# Busboard_v4.net
KiCad netlist of a schematic drawn in EAGLE
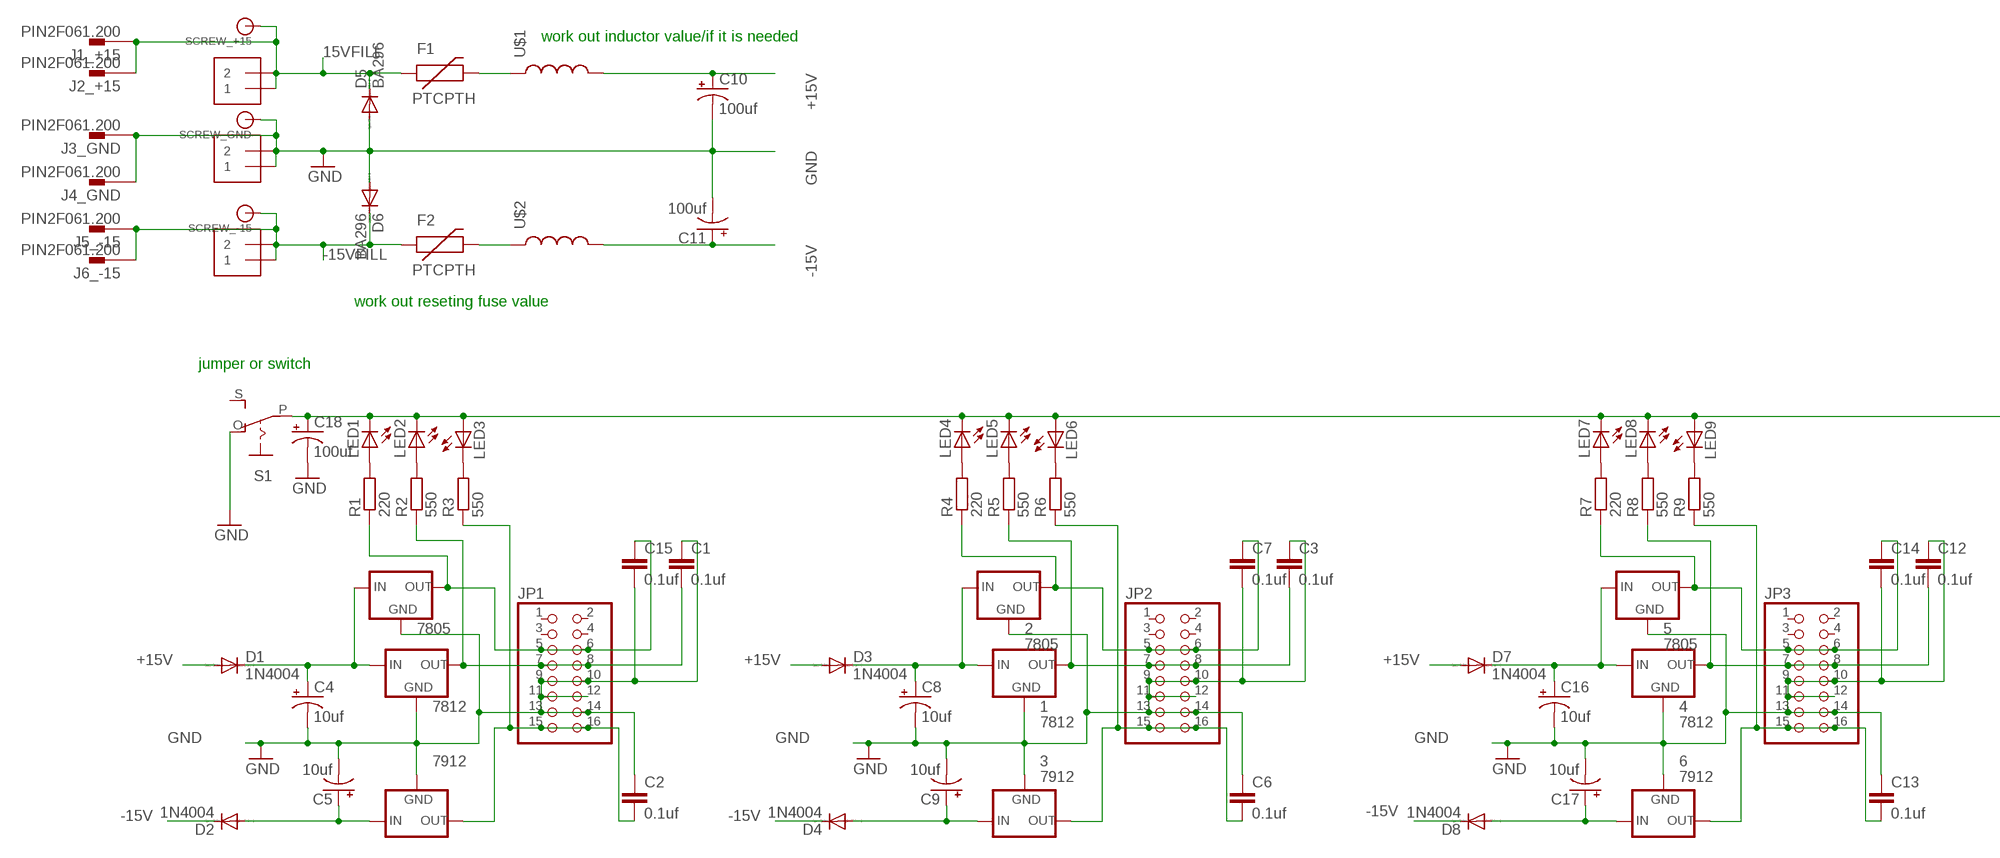
[diagram p0: schematic, sheet 1, part 1 of 2]
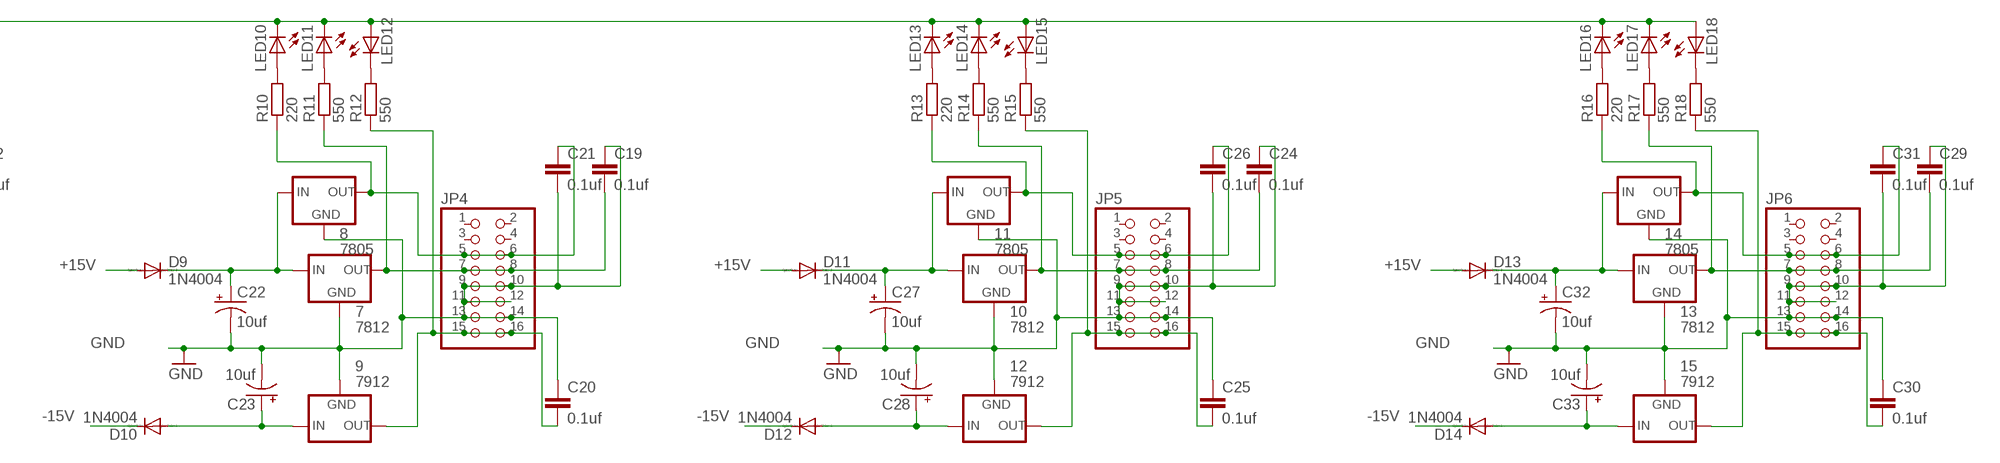
[diagram p1: schematic, sheet 1, part 2 of 2]

(export (version "E")
  (design (tool "Eeschema 10.0.6"))
  (components
    (comp (ref "+15V_DC_IN")
      (value "1X2-3.5MM")
      (footprint "eagle-import:1X2-3.5MM")
      (libsource (lib "eagle-import") (part "1X2-3.5MM"))
    )
    (comp (ref "-15V_DC_IN")
      (value "1X2-3.5MM")
      (footprint "eagle-import:1X2-3.5MM")
      (libsource (lib "eagle-import") (part "1X2-3.5MM"))
    )
    (comp (ref "1")
      (value "7812")
      (footprint "eagle-import:78MXXS")
      (libsource (lib "eagle-import") (part "78MXXS"))
    )
    (comp (ref "2")
      (value "7805")
      (footprint "eagle-import:78MXXS")
      (libsource (lib "eagle-import") (part "78MXXS"))
    )
    (comp (ref "3")
      (value "7912")
      (footprint "eagle-import:79XXS")
      (libsource (lib "eagle-import") (part "79XXS"))
    )
    (comp (ref "4")
      (value "7812")
      (footprint "eagle-import:78MXXS")
      (libsource (lib "eagle-import") (part "78MXXS"))
    )
    (comp (ref "5")
      (value "7805")
      (footprint "eagle-import:78MXXS")
      (libsource (lib "eagle-import") (part "78MXXS"))
    )
    (comp (ref "6")
      (value "7912")
      (footprint "eagle-import:79XXS")
      (libsource (lib "eagle-import") (part "79XXS"))
    )
    (comp (ref "7")
      (value "7812")
      (footprint "eagle-import:78MXXS")
      (libsource (lib "eagle-import") (part "78MXXS"))
    )
    (comp (ref "8")
      (value "7805")
      (footprint "eagle-import:78MXXS")
      (libsource (lib "eagle-import") (part "78MXXS"))
    )
    (comp (ref "9")
      (value "7912")
      (footprint "eagle-import:79XXS")
      (libsource (lib "eagle-import") (part "79XXS"))
    )
    (comp (ref "10")
      (value "7812")
      (footprint "eagle-import:78MXXS")
      (libsource (lib "eagle-import") (part "78MXXS"))
    )
    (comp (ref "11")
      (value "7805")
      (footprint "eagle-import:78MXXS")
      (libsource (lib "eagle-import") (part "78MXXS"))
    )
    (comp (ref "12")
      (value "7912")
      (footprint "eagle-import:79XXS")
      (libsource (lib "eagle-import") (part "79XXS"))
    )
    (comp (ref "13")
      (value "7812")
      (footprint "eagle-import:78MXXS")
      (libsource (lib "eagle-import") (part "78MXXS"))
    )
    (comp (ref "14")
      (value "7805")
      (footprint "eagle-import:78MXXS")
      (libsource (lib "eagle-import") (part "78MXXS"))
    )
    (comp (ref "15")
      (value "7912")
      (footprint "eagle-import:79XXS")
      (libsource (lib "eagle-import") (part "79XXS"))
    )
    (comp (ref "7805")
      (value "78MXXS")
      (footprint "eagle-import:78MXXS")
      (libsource (lib "eagle-import") (part "78MXXS"))
    )
    (comp (ref "7812")
      (value "78MXXS")
      (footprint "eagle-import:78MXXS")
      (libsource (lib "eagle-import") (part "78MXXS"))
    )
    (comp (ref "7912")
      (value "79XXS")
      (footprint "eagle-import:79XXS")
      (libsource (lib "eagle-import") (part "79XXS"))
    )
    (comp (ref "C1")
      (value "0.1uf")
      (footprint "eagle-import:CAP-PTH-SMALL-KIT")
      (libsource (lib "eagle-import") (part "0.1UF-50V-20%(PTH)KIT-EZ"))
    )
    (comp (ref "C2")
      (value "0.1uf")
      (footprint "eagle-import:CAP-PTH-SMALL-KIT")
      (libsource (lib "eagle-import") (part "0.1UF-50V-20%(PTH)KIT-EZ"))
    )
    (comp (ref "C3")
      (value "0.1uf")
      (footprint "eagle-import:CAP-PTH-SMALL-KIT")
      (libsource (lib "eagle-import") (part "0.1UF-50V-20%(PTH)KIT-EZ"))
    )
    (comp (ref "C4")
      (value "10uf")
      (footprint "eagle-import:CPOL-RADIAL-10UF-25V")
      (libsource (lib "eagle-import") (part "10UF-25V-20%(PTH)"))
    )
    (comp (ref "C5")
      (value "10uf")
      (footprint "eagle-import:CPOL-RADIAL-10UF-25V")
      (libsource (lib "eagle-import") (part "10UF-25V-20%(PTH)"))
    )
    (comp (ref "C6")
      (value "0.1uf")
      (footprint "eagle-import:CAP-PTH-SMALL-KIT")
      (libsource (lib "eagle-import") (part "0.1UF-50V-20%(PTH)KIT-EZ"))
    )
    (comp (ref "C7")
      (value "0.1uf")
      (footprint "eagle-import:CAP-PTH-SMALL-KIT")
      (libsource (lib "eagle-import") (part "0.1UF-50V-20%(PTH)KIT-EZ"))
    )
    (comp (ref "C8")
      (value "10uf")
      (footprint "eagle-import:CPOL-RADIAL-10UF-25V")
      (libsource (lib "eagle-import") (part "10UF-25V-20%(PTH)"))
    )
    (comp (ref "C9")
      (value "10uf")
      (footprint "eagle-import:CPOL-RADIAL-10UF-25V")
      (libsource (lib "eagle-import") (part "10UF-25V-20%(PTH)"))
    )
    (comp (ref "C10")
      (value "100uf")
      (footprint "eagle-import:CPOL-RADIAL-100UF-25V")
      (libsource (lib "eagle-import") (part "100UF-25V-20%(PTH)"))
    )
    (comp (ref "C11")
      (value "100uf")
      (footprint "eagle-import:CPOL-RADIAL-100UF-25V")
      (libsource (lib "eagle-import") (part "100UF-25V-20%(PTH)"))
    )
    (comp (ref "C12")
      (value "0.1uf")
      (footprint "eagle-import:CAP-PTH-SMALL-KIT")
      (libsource (lib "eagle-import") (part "0.1UF-50V-20%(PTH)KIT-EZ"))
    )
    (comp (ref "C13")
      (value "0.1uf")
      (footprint "eagle-import:CAP-PTH-SMALL-KIT")
      (libsource (lib "eagle-import") (part "0.1UF-50V-20%(PTH)KIT-EZ"))
    )
    (comp (ref "C14")
      (value "0.1uf")
      (footprint "eagle-import:CAP-PTH-SMALL-KIT")
      (libsource (lib "eagle-import") (part "0.1UF-50V-20%(PTH)KIT-EZ"))
    )
    (comp (ref "C15")
      (value "0.1uf")
      (footprint "eagle-import:CAP-PTH-SMALL-KIT")
      (libsource (lib "eagle-import") (part "0.1UF-50V-20%(PTH)KIT-EZ"))
    )
    (comp (ref "C16")
      (value "10uf")
      (footprint "eagle-import:CPOL-RADIAL-10UF-25V")
      (libsource (lib "eagle-import") (part "10UF-25V-20%(PTH)"))
    )
    (comp (ref "C17")
      (value "10uf")
      (footprint "eagle-import:CPOL-RADIAL-10UF-25V")
      (libsource (lib "eagle-import") (part "10UF-25V-20%(PTH)"))
    )
    (comp (ref "C18")
      (value "100uf")
      (footprint "eagle-import:CPOL-RADIAL-100UF-25V")
      (libsource (lib "eagle-import") (part "100UF-25V-20%(PTH)"))
    )
    (comp (ref "C19")
      (value "0.1uf")
      (footprint "eagle-import:CAP-PTH-SMALL-KIT")
      (libsource (lib "eagle-import") (part "0.1UF-50V-20%(PTH)KIT-EZ"))
    )
    (comp (ref "C20")
      (value "0.1uf")
      (footprint "eagle-import:CAP-PTH-SMALL-KIT")
      (libsource (lib "eagle-import") (part "0.1UF-50V-20%(PTH)KIT-EZ"))
    )
    (comp (ref "C21")
      (value "0.1uf")
      (footprint "eagle-import:CAP-PTH-SMALL-KIT")
      (libsource (lib "eagle-import") (part "0.1UF-50V-20%(PTH)KIT-EZ"))
    )
    (comp (ref "C22")
      (value "10uf")
      (footprint "eagle-import:CPOL-RADIAL-10UF-25V")
      (libsource (lib "eagle-import") (part "10UF-25V-20%(PTH)"))
    )
    (comp (ref "C23")
      (value "10uf")
      (footprint "eagle-import:CPOL-RADIAL-10UF-25V")
      (libsource (lib "eagle-import") (part "10UF-25V-20%(PTH)"))
    )
    (comp (ref "C24")
      (value "0.1uf")
      (footprint "eagle-import:CAP-PTH-SMALL-KIT")
      (libsource (lib "eagle-import") (part "0.1UF-50V-20%(PTH)KIT-EZ"))
    )
    (comp (ref "C25")
      (value "0.1uf")
      (footprint "eagle-import:CAP-PTH-SMALL-KIT")
      (libsource (lib "eagle-import") (part "0.1UF-50V-20%(PTH)KIT-EZ"))
    )
    (comp (ref "C26")
      (value "0.1uf")
      (footprint "eagle-import:CAP-PTH-SMALL-KIT")
      (libsource (lib "eagle-import") (part "0.1UF-50V-20%(PTH)KIT-EZ"))
    )
    (comp (ref "C27")
      (value "10uf")
      (footprint "eagle-import:CPOL-RADIAL-10UF-25V")
      (libsource (lib "eagle-import") (part "10UF-25V-20%(PTH)"))
    )
    (comp (ref "C28")
      (value "10uf")
      (footprint "eagle-import:CPOL-RADIAL-10UF-25V")
      (libsource (lib "eagle-import") (part "10UF-25V-20%(PTH)"))
    )
    (comp (ref "C29")
      (value "0.1uf")
      (footprint "eagle-import:CAP-PTH-SMALL-KIT")
      (libsource (lib "eagle-import") (part "0.1UF-50V-20%(PTH)KIT-EZ"))
    )
    (comp (ref "C30")
      (value "0.1uf")
      (footprint "eagle-import:CAP-PTH-SMALL-KIT")
      (libsource (lib "eagle-import") (part "0.1UF-50V-20%(PTH)KIT-EZ"))
    )
    (comp (ref "C31")
      (value "0.1uf")
      (footprint "eagle-import:CAP-PTH-SMALL-KIT")
      (libsource (lib "eagle-import") (part "0.1UF-50V-20%(PTH)KIT-EZ"))
    )
    (comp (ref "C32")
      (value "10uf")
      (footprint "eagle-import:CPOL-RADIAL-10UF-25V")
      (libsource (lib "eagle-import") (part "10UF-25V-20%(PTH)"))
    )
    (comp (ref "C33")
      (value "10uf")
      (footprint "eagle-import:CPOL-RADIAL-10UF-25V")
      (libsource (lib "eagle-import") (part "10UF-25V-20%(PTH)"))
    )
    (comp (ref "D1")
      (value "1N4004")
      (footprint "eagle-import:DO41-10")
      (libsource (lib "eagle-import") (part "1N4004"))
    )
    (comp (ref "D2")
      (value "1N4004")
      (footprint "eagle-import:DO41-10")
      (libsource (lib "eagle-import") (part "1N4004"))
    )
    (comp (ref "D3")
      (value "1N4004")
      (footprint "eagle-import:DO41-10")
      (libsource (lib "eagle-import") (part "1N4004"))
    )
    (comp (ref "D4")
      (value "1N4004")
      (footprint "eagle-import:DO41-10")
      (libsource (lib "eagle-import") (part "1N4004"))
    )
    (comp (ref "D5")
      (value "BA296")
      (footprint "eagle-import:P2-15")
      (libsource (lib "eagle-import") (part "BA296"))
    )
    (comp (ref "D6")
      (value "BA296")
      (footprint "eagle-import:P2-15")
      (libsource (lib "eagle-import") (part "BA296"))
    )
    (comp (ref "D7")
      (value "1N4004")
      (footprint "eagle-import:DO41-10")
      (libsource (lib "eagle-import") (part "1N4004"))
    )
    (comp (ref "D8")
      (value "1N4004")
      (footprint "eagle-import:DO41-10")
      (libsource (lib "eagle-import") (part "1N4004"))
    )
    (comp (ref "D9")
      (value "1N4004")
      (footprint "eagle-import:DO41-10")
      (libsource (lib "eagle-import") (part "1N4004"))
    )
    (comp (ref "D10")
      (value "1N4004")
      (footprint "eagle-import:DO41-10")
      (libsource (lib "eagle-import") (part "1N4004"))
    )
    (comp (ref "D11")
      (value "1N4004")
      (footprint "eagle-import:DO41-10")
      (libsource (lib "eagle-import") (part "1N4004"))
    )
    (comp (ref "D12")
      (value "1N4004")
      (footprint "eagle-import:DO41-10")
      (libsource (lib "eagle-import") (part "1N4004"))
    )
    (comp (ref "D13")
      (value "1N4004")
      (footprint "eagle-import:DO41-10")
      (libsource (lib "eagle-import") (part "1N4004"))
    )
    (comp (ref "D14")
      (value "1N4004")
      (footprint "eagle-import:DO41-10")
      (libsource (lib "eagle-import") (part "1N4004"))
    )
    (comp (ref "F1")
      (value "PTCPTH")
      (footprint "eagle-import:PTC")
      (libsource (lib "eagle-import") (part "PTCPTH"))
    )
    (comp (ref "F2")
      (value "PTCPTH")
      (footprint "eagle-import:PTC")
      (libsource (lib "eagle-import") (part "PTCPTH"))
    )
    (comp (ref "GND_IN")
      (value "1X2-3.5MM")
      (footprint "eagle-import:1X2-3.5MM")
      (libsource (lib "eagle-import") (part "1X2-3.5MM"))
    )
    (comp (ref "J1_+15")
      (value "PIN2F061.200")
      (footprint "eagle-import:F061.200")
      (libsource (lib "eagle-import") (part "PIN2F061.200"))
    )
    (comp (ref "J2_+15")
      (value "PIN2F061.200")
      (footprint "eagle-import:F061.200")
      (libsource (lib "eagle-import") (part "PIN2F061.200"))
    )
    (comp (ref "J3_GND")
      (value "PIN2F061.200")
      (footprint "eagle-import:F061.200")
      (libsource (lib "eagle-import") (part "PIN2F061.200"))
    )
    (comp (ref "J4_GND")
      (value "PIN2F061.200")
      (footprint "eagle-import:F061.200")
      (libsource (lib "eagle-import") (part "PIN2F061.200"))
    )
    (comp (ref "J5_-15")
      (value "PIN2F061.200")
      (footprint "eagle-import:F061.200")
      (libsource (lib "eagle-import") (part "PIN2F061.200"))
    )
    (comp (ref "J6_-15")
      (value "PIN2F061.200")
      (footprint "eagle-import:F061.200")
      (libsource (lib "eagle-import") (part "PIN2F061.200"))
    )
    (comp (ref "JP1")
      (value "PINHD-2X8")
      (footprint "eagle-import:2X08")
      (libsource (lib "eagle-import") (part "PINHD-2X8"))
    )
    (comp (ref "JP2")
      (value "PINHD-2X8")
      (footprint "eagle-import:2X08")
      (libsource (lib "eagle-import") (part "PINHD-2X8"))
    )
    (comp (ref "JP3")
      (value "PINHD-2X8")
      (footprint "eagle-import:2X08")
      (libsource (lib "eagle-import") (part "PINHD-2X8"))
    )
    (comp (ref "JP4")
      (value "PINHD-2X8")
      (footprint "eagle-import:2X08")
      (libsource (lib "eagle-import") (part "PINHD-2X8"))
    )
    (comp (ref "JP5")
      (value "PINHD-2X8")
      (footprint "eagle-import:2X08")
      (libsource (lib "eagle-import") (part "PINHD-2X8"))
    )
    (comp (ref "JP6")
      (value "PINHD-2X8")
      (footprint "eagle-import:2X08")
      (libsource (lib "eagle-import") (part "PINHD-2X8"))
    )
    (comp (ref "LED1")
      (value "LED3MM")
      (footprint "eagle-import:LED3MM")
      (libsource (lib "eagle-import") (part "LED3MM"))
    )
    (comp (ref "LED2")
      (value "LED3MM")
      (footprint "eagle-import:LED3MM")
      (libsource (lib "eagle-import") (part "LED3MM"))
    )
    (comp (ref "LED3")
      (value "LED3MM")
      (footprint "eagle-import:LED3MM")
      (libsource (lib "eagle-import") (part "LED3MM"))
    )
    (comp (ref "LED4")
      (value "LED3MM")
      (footprint "eagle-import:LED3MM")
      (libsource (lib "eagle-import") (part "LED3MM"))
    )
    (comp (ref "LED5")
      (value "LED3MM")
      (footprint "eagle-import:LED3MM")
      (libsource (lib "eagle-import") (part "LED3MM"))
    )
    (comp (ref "LED6")
      (value "LED3MM")
      (footprint "eagle-import:LED3MM")
      (libsource (lib "eagle-import") (part "LED3MM"))
    )
    (comp (ref "LED7")
      (value "LED3MM")
      (footprint "eagle-import:LED3MM")
      (libsource (lib "eagle-import") (part "LED3MM"))
    )
    (comp (ref "LED8")
      (value "LED3MM")
      (footprint "eagle-import:LED3MM")
      (libsource (lib "eagle-import") (part "LED3MM"))
    )
    (comp (ref "LED9")
      (value "LED3MM")
      (footprint "eagle-import:LED3MM")
      (libsource (lib "eagle-import") (part "LED3MM"))
    )
    (comp (ref "LED10")
      (value "LED3MM")
      (footprint "eagle-import:LED3MM")
      (libsource (lib "eagle-import") (part "LED3MM"))
    )
    (comp (ref "LED11")
      (value "LED3MM")
      (footprint "eagle-import:LED3MM")
      (libsource (lib "eagle-import") (part "LED3MM"))
    )
    (comp (ref "LED12")
      (value "LED3MM")
      (footprint "eagle-import:LED3MM")
      (libsource (lib "eagle-import") (part "LED3MM"))
    )
    (comp (ref "LED13")
      (value "LED3MM")
      (footprint "eagle-import:LED3MM")
      (libsource (lib "eagle-import") (part "LED3MM"))
    )
    (comp (ref "LED14")
      (value "LED3MM")
      (footprint "eagle-import:LED3MM")
      (libsource (lib "eagle-import") (part "LED3MM"))
    )
    (comp (ref "LED15")
      (value "LED3MM")
      (footprint "eagle-import:LED3MM")
      (libsource (lib "eagle-import") (part "LED3MM"))
    )
    (comp (ref "LED16")
      (value "LED3MM")
      (footprint "eagle-import:LED3MM")
      (libsource (lib "eagle-import") (part "LED3MM"))
    )
    (comp (ref "LED17")
      (value "LED3MM")
      (footprint "eagle-import:LED3MM")
      (libsource (lib "eagle-import") (part "LED3MM"))
    )
    (comp (ref "LED18")
      (value "LED3MM")
      (footprint "eagle-import:LED3MM")
      (libsource (lib "eagle-import") (part "LED3MM"))
    )
    (comp (ref "R1")
      (value "220")
      (footprint "eagle-import:0207_5V")
      (libsource (lib "eagle-import") (part "R-EU_0207/5V"))
    )
    (comp (ref "R2")
      (value "550")
      (footprint "eagle-import:0207_5V")
      (libsource (lib "eagle-import") (part "R-EU_0207/5V"))
    )
    (comp (ref "R3")
      (value "550")
      (footprint "eagle-import:0207_5V")
      (libsource (lib "eagle-import") (part "R-EU_0207/5V"))
    )
    (comp (ref "R4")
      (value "220")
      (footprint "eagle-import:0207_5V")
      (libsource (lib "eagle-import") (part "R-EU_0207/5V"))
    )
    (comp (ref "R5")
      (value "550")
      (footprint "eagle-import:0207_5V")
      (libsource (lib "eagle-import") (part "R-EU_0207/5V"))
    )
    (comp (ref "R6")
      (value "550")
      (footprint "eagle-import:0207_5V")
      (libsource (lib "eagle-import") (part "R-EU_0207/5V"))
    )
    (comp (ref "R7")
      (value "220")
      (footprint "eagle-import:0207_5V")
      (libsource (lib "eagle-import") (part "R-EU_0207/5V"))
    )
    (comp (ref "R8")
      (value "550")
      (footprint "eagle-import:0207_5V")
      (libsource (lib "eagle-import") (part "R-EU_0207/5V"))
    )
    (comp (ref "R9")
      (value "550")
      (footprint "eagle-import:0207_5V")
      (libsource (lib "eagle-import") (part "R-EU_0207/5V"))
    )
    (comp (ref "R10")
      (value "220")
      (footprint "eagle-import:0207_5V")
      (libsource (lib "eagle-import") (part "R-EU_0207/5V"))
    )
    (comp (ref "R11")
      (value "550")
      (footprint "eagle-import:0207_5V")
      (libsource (lib "eagle-import") (part "R-EU_0207/5V"))
    )
    (comp (ref "R12")
      (value "550")
      (footprint "eagle-import:0207_5V")
      (libsource (lib "eagle-import") (part "R-EU_0207/5V"))
    )
    (comp (ref "R13")
      (value "220")
      (footprint "eagle-import:0207_5V")
      (libsource (lib "eagle-import") (part "R-EU_0207/5V"))
    )
    (comp (ref "R14")
      (value "550")
      (footprint "eagle-import:0207_5V")
      (libsource (lib "eagle-import") (part "R-EU_0207/5V"))
    )
    (comp (ref "R15")
      (value "550")
      (footprint "eagle-import:0207_5V")
      (libsource (lib "eagle-import") (part "R-EU_0207/5V"))
    )
    (comp (ref "R16")
      (value "220")
      (footprint "eagle-import:0207_5V")
      (libsource (lib "eagle-import") (part "R-EU_0207/5V"))
    )
    (comp (ref "R17")
      (value "550")
      (footprint "eagle-import:0207_5V")
      (libsource (lib "eagle-import") (part "R-EU_0207/5V"))
    )
    (comp (ref "R18")
      (value "550")
      (footprint "eagle-import:0207_5V")
      (libsource (lib "eagle-import") (part "R-EU_0207/5V"))
    )
    (comp (ref "S1")
      (value "EG1218S")
      (footprint "eagle-import:EG1218")
      (libsource (lib "eagle-import") (part "EG1218S"))
    )
    (comp (ref "SCREW_+15")
      (value "BANANA_CONN")
      (footprint "eagle-import:BANANA_CONN")
      (libsource (lib "eagle-import") (part "BANANA_CONN"))
    )
    (comp (ref "SCREW_-15")
      (value "BANANA_CONN")
      (footprint "eagle-import:BANANA_CONN")
      (libsource (lib "eagle-import") (part "BANANA_CONN"))
    )
    (comp (ref "SCREW_GND")
      (value "BANANA_CONN")
      (footprint "eagle-import:BANANA_CONN")
      (libsource (lib "eagle-import") (part "BANANA_CONN"))
    )
    (comp (ref "U$1")
      (value "INDUCTORRLB0912")
      (footprint "eagle-import:RLB0912")
      (libsource (lib "eagle-import") (part "INDUCTORRLB0912"))
    )
    (comp (ref "U$2")
      (value "INDUCTORRLB0912")
      (footprint "eagle-import:RLB0912")
      (libsource (lib "eagle-import") (part "INDUCTORRLB0912"))
    )
  )
  (nets
    (net (code "1") (name "/+15V") (class "Default")
      (node (ref "C10") (pin "1") (pinfunction "+_1") (pintype "passive"))
      (node (ref "D1") (pin "A") (pinfunction "A_A") (pintype "passive"))
      (node (ref "D11") (pin "A") (pinfunction "A_A") (pintype "passive"))
      (node (ref "D13") (pin "A") (pinfunction "A_A") (pintype "passive"))
      (node (ref "D3") (pin "A") (pinfunction "A_A") (pintype "passive"))
      (node (ref "D7") (pin "A") (pinfunction "A_A") (pintype "passive"))
      (node (ref "D9") (pin "A") (pinfunction "A_A") (pintype "passive"))
      (node (ref "U$1") (pin "2") (pinfunction "2_2") (pintype "passive"))
    )
    (net (code "2") (name "/-15V") (class "Default")
      (node (ref "C11") (pin "1") (pinfunction "+_1") (pintype "passive"))
      (node (ref "D10") (pin "C") (pinfunction "C_C") (pintype "passive"))
      (node (ref "D12") (pin "C") (pinfunction "C_C") (pintype "passive"))
      (node (ref "D14") (pin "C") (pinfunction "C_C") (pintype "passive"))
      (node (ref "D2") (pin "C") (pinfunction "C_C") (pintype "passive"))
      (node (ref "D4") (pin "C") (pinfunction "C_C") (pintype "passive"))
      (node (ref "D8") (pin "C") (pinfunction "C_C") (pintype "passive"))
      (node (ref "U$2") (pin "2") (pinfunction "2_2") (pintype "passive"))
    )
    (net (code "3") (name "/-15VFILL") (class "Default")
      (node (ref "-15V_DC_IN") (pin "1") (pinfunction "1_1") (pintype "passive"))
      (node (ref "-15V_DC_IN") (pin "2") (pinfunction "2_2") (pintype "passive"))
      (node (ref "D6") (pin "C") (pinfunction "C_C") (pintype "passive"))
      (node (ref "F2") (pin "P$1") (pinfunction "1_P$1") (pintype "bidirectional"))
      (node (ref "J5_-15") (pin "1A") (pinfunction "1_1A") (pintype "passive"))
      (node (ref "J5_-15") (pin "1B") (pinfunction "1_1B") (pintype "passive"))
      (node (ref "J6_-15") (pin "1A") (pinfunction "1_1A") (pintype "passive"))
      (node (ref "J6_-15") (pin "1B") (pinfunction "1_1B") (pintype "passive"))
      (node (ref "SCREW_-15") (pin "P$1") (pinfunction "1_P$1") (pintype "passive"))
    )
    (net (code "4") (name "/15VFILL") (class "Default")
      (node (ref "+15V_DC_IN") (pin "1") (pinfunction "1_1") (pintype "passive"))
      (node (ref "+15V_DC_IN") (pin "2") (pinfunction "2_2") (pintype "passive"))
      (node (ref "D5") (pin "C") (pinfunction "C_C") (pintype "passive"))
      (node (ref "F1") (pin "P$1") (pinfunction "1_P$1") (pintype "bidirectional"))
      (node (ref "J1_+15") (pin "1A") (pinfunction "1_1A") (pintype "passive"))
      (node (ref "J1_+15") (pin "1B") (pinfunction "1_1B") (pintype "passive"))
      (node (ref "J2_+15") (pin "1A") (pinfunction "1_1A") (pintype "passive"))
      (node (ref "J2_+15") (pin "1B") (pinfunction "1_1B") (pintype "passive"))
      (node (ref "SCREW_+15") (pin "P$1") (pinfunction "1_P$1") (pintype "passive"))
    )
    (net (code "5") (name "GND") (class "Default")
      (node (ref "1") (pin "GND") (pinfunction "GND_GND") (pintype "input"))
      (node (ref "10") (pin "GND") (pinfunction "GND_GND") (pintype "input"))
      (node (ref "11") (pin "GND") (pinfunction "GND_GND") (pintype "input"))
      (node (ref "12") (pin "GND") (pinfunction "GND_GND") (pintype "input"))
      (node (ref "13") (pin "GND") (pinfunction "GND_GND") (pintype "input"))
      (node (ref "14") (pin "GND") (pinfunction "GND_GND") (pintype "input"))
      (node (ref "15") (pin "GND") (pinfunction "GND_GND") (pintype "input"))
      (node (ref "2") (pin "GND") (pinfunction "GND_GND") (pintype "input"))
      (node (ref "3") (pin "GND") (pinfunction "GND_GND") (pintype "input"))
      (node (ref "4") (pin "GND") (pinfunction "GND_GND") (pintype "input"))
      (node (ref "5") (pin "GND") (pinfunction "GND_GND") (pintype "input"))
      (node (ref "6") (pin "GND") (pinfunction "GND_GND") (pintype "input"))
      (node (ref "7") (pin "GND") (pinfunction "GND_GND") (pintype "input"))
      (node (ref "7805") (pin "GND") (pinfunction "GND_GND") (pintype "input"))
      (node (ref "7812") (pin "GND") (pinfunction "GND_GND") (pintype "input"))
      (node (ref "7912") (pin "GND") (pinfunction "GND_GND") (pintype "input"))
      (node (ref "8") (pin "GND") (pinfunction "GND_GND") (pintype "input"))
      (node (ref "9") (pin "GND") (pinfunction "GND_GND") (pintype "input"))
      (node (ref "C1") (pin "1") (pinfunction "1_1") (pintype "passive"))
      (node (ref "C10") (pin "2") (pinfunction "-_2") (pintype "passive"))
      (node (ref "C11") (pin "2") (pinfunction "-_2") (pintype "passive"))
      (node (ref "C12") (pin "1") (pinfunction "1_1") (pintype "passive"))
      (node (ref "C13") (pin "1") (pinfunction "1_1") (pintype "passive"))
      (node (ref "C14") (pin "2") (pinfunction "2_2") (pintype "passive"))
      (node (ref "C15") (pin "2") (pinfunction "2_2") (pintype "passive"))
      (node (ref "C16") (pin "2") (pinfunction "-_2") (pintype "passive"))
      (node (ref "C17") (pin "2") (pinfunction "-_2") (pintype "passive"))
      (node (ref "C18") (pin "2") (pinfunction "-_2") (pintype "passive"))
      (node (ref "C19") (pin "1") (pinfunction "1_1") (pintype "passive"))
      (node (ref "C2") (pin "1") (pinfunction "1_1") (pintype "passive"))
      (node (ref "C20") (pin "1") (pinfunction "1_1") (pintype "passive"))
      (node (ref "C21") (pin "2") (pinfunction "2_2") (pintype "passive"))
      (node (ref "C22") (pin "2") (pinfunction "-_2") (pintype "passive"))
      (node (ref "C23") (pin "2") (pinfunction "-_2") (pintype "passive"))
      (node (ref "C24") (pin "1") (pinfunction "1_1") (pintype "passive"))
      (node (ref "C25") (pin "1") (pinfunction "1_1") (pintype "passive"))
      (node (ref "C26") (pin "2") (pinfunction "2_2") (pintype "passive"))
      (node (ref "C27") (pin "2") (pinfunction "-_2") (pintype "passive"))
      (node (ref "C28") (pin "2") (pinfunction "-_2") (pintype "passive"))
      (node (ref "C29") (pin "1") (pinfunction "1_1") (pintype "passive"))
      (node (ref "C3") (pin "1") (pinfunction "1_1") (pintype "passive"))
      (node (ref "C30") (pin "1") (pinfunction "1_1") (pintype "passive"))
      (node (ref "C31") (pin "2") (pinfunction "2_2") (pintype "passive"))
      (node (ref "C32") (pin "2") (pinfunction "-_2") (pintype "passive"))
      (node (ref "C33") (pin "2") (pinfunction "-_2") (pintype "passive"))
      (node (ref "C4") (pin "2") (pinfunction "-_2") (pintype "passive"))
      (node (ref "C5") (pin "2") (pinfunction "-_2") (pintype "passive"))
      (node (ref "C6") (pin "1") (pinfunction "1_1") (pintype "passive"))
      (node (ref "C7") (pin "2") (pinfunction "2_2") (pintype "passive"))
      (node (ref "C8") (pin "2") (pinfunction "-_2") (pintype "passive"))
      (node (ref "C9") (pin "2") (pinfunction "-_2") (pintype "passive"))
      (node (ref "D5") (pin "A") (pinfunction "A_A") (pintype "passive"))
      (node (ref "D6") (pin "A") (pinfunction "A_A") (pintype "passive"))
      (node (ref "GND_IN") (pin "1") (pinfunction "1_1") (pintype "passive"))
      (node (ref "GND_IN") (pin "2") (pinfunction "2_2") (pintype "passive"))
      (node (ref "J3_GND") (pin "1A") (pinfunction "1_1A") (pintype "passive"))
      (node (ref "J3_GND") (pin "1B") (pinfunction "1_1B") (pintype "passive"))
      (node (ref "J4_GND") (pin "1A") (pinfunction "1_1A") (pintype "passive"))
      (node (ref "J4_GND") (pin "1B") (pinfunction "1_1B") (pintype "passive"))
      (node (ref "JP1") (pin "10") (pinfunction "10_10") (pintype "passive"))
      (node (ref "JP1") (pin "11") (pinfunction "11_11") (pintype "passive"))
      (node (ref "JP1") (pin "12") (pinfunction "12_12") (pintype "passive"))
      (node (ref "JP1") (pin "13") (pinfunction "13_13") (pintype "passive"))
      (node (ref "JP1") (pin "14") (pinfunction "14_14") (pintype "passive"))
      (node (ref "JP1") (pin "9") (pinfunction "9_9") (pintype "passive"))
      (node (ref "JP2") (pin "10") (pinfunction "10_10") (pintype "passive"))
      (node (ref "JP2") (pin "11") (pinfunction "11_11") (pintype "passive"))
      (node (ref "JP2") (pin "12") (pinfunction "12_12") (pintype "passive"))
      (node (ref "JP2") (pin "13") (pinfunction "13_13") (pintype "passive"))
      (node (ref "JP2") (pin "14") (pinfunction "14_14") (pintype "passive"))
      (node (ref "JP2") (pin "9") (pinfunction "9_9") (pintype "passive"))
      (node (ref "JP3") (pin "10") (pinfunction "10_10") (pintype "passive"))
      (node (ref "JP3") (pin "11") (pinfunction "11_11") (pintype "passive"))
      (node (ref "JP3") (pin "12") (pinfunction "12_12") (pintype "passive"))
      (node (ref "JP3") (pin "13") (pinfunction "13_13") (pintype "passive"))
      (node (ref "JP3") (pin "14") (pinfunction "14_14") (pintype "passive"))
      (node (ref "JP3") (pin "9") (pinfunction "9_9") (pintype "passive"))
      (node (ref "JP4") (pin "10") (pinfunction "10_10") (pintype "passive"))
      (node (ref "JP4") (pin "11") (pinfunction "11_11") (pintype "passive"))
      (node (ref "JP4") (pin "12") (pinfunction "12_12") (pintype "passive"))
      (node (ref "JP4") (pin "13") (pinfunction "13_13") (pintype "passive"))
      (node (ref "JP4") (pin "14") (pinfunction "14_14") (pintype "passive"))
      (node (ref "JP4") (pin "9") (pinfunction "9_9") (pintype "passive"))
      (node (ref "JP5") (pin "10") (pinfunction "10_10") (pintype "passive"))
      (node (ref "JP5") (pin "11") (pinfunction "11_11") (pintype "passive"))
      (node (ref "JP5") (pin "12") (pinfunction "12_12") (pintype "passive"))
      (node (ref "JP5") (pin "13") (pinfunction "13_13") (pintype "passive"))
      (node (ref "JP5") (pin "14") (pinfunction "14_14") (pintype "passive"))
      (node (ref "JP5") (pin "9") (pinfunction "9_9") (pintype "passive"))
      (node (ref "JP6") (pin "10") (pinfunction "10_10") (pintype "passive"))
      (node (ref "JP6") (pin "11") (pinfunction "11_11") (pintype "passive"))
      (node (ref "JP6") (pin "12") (pinfunction "12_12") (pintype "passive"))
      (node (ref "JP6") (pin "13") (pinfunction "13_13") (pintype "passive"))
      (node (ref "JP6") (pin "14") (pinfunction "14_14") (pintype "passive"))
      (node (ref "JP6") (pin "9") (pinfunction "9_9") (pintype "passive"))
      (node (ref "S1") (pin "O") (pinfunction "O_O") (pintype "passive"))
      (node (ref "SCREW_GND") (pin "P$1") (pinfunction "1_P$1") (pintype "passive"))
    )
    (net (code "6") (name "Net-(1-PadOUT)") (class "Default")
      (node (ref "1") (pin "OUT") (pinfunction "OUT_OUT") (pintype "passive"))
      (node (ref "C3") (pin "2") (pinfunction "2_2") (pintype "passive"))
      (node (ref "JP2") (pin "7") (pinfunction "7_7") (pintype "passive"))
      (node (ref "JP2") (pin "8") (pinfunction "8_8") (pintype "passive"))
      (node (ref "R5") (pin "1") (pinfunction "1_1") (pintype "passive"))
    )
    (net (code "7") (name "Net-(2-PadOUT)") (class "Default")
      (node (ref "2") (pin "OUT") (pinfunction "OUT_OUT") (pintype "passive"))
      (node (ref "C7") (pin "1") (pinfunction "1_1") (pintype "passive"))
      (node (ref "JP2") (pin "5") (pinfunction "5_5") (pintype "passive"))
      (node (ref "JP2") (pin "6") (pinfunction "6_6") (pintype "passive"))
      (node (ref "R4") (pin "1") (pinfunction "1_1") (pintype "passive"))
    )
    (net (code "8") (name "Net-(3-PadOUT)") (class "Default")
      (node (ref "3") (pin "OUT") (pinfunction "OUT_OUT") (pintype "passive"))
      (node (ref "C6") (pin "2") (pinfunction "2_2") (pintype "passive"))
      (node (ref "JP2") (pin "15") (pinfunction "15_15") (pintype "passive"))
      (node (ref "JP2") (pin "16") (pinfunction "16_16") (pintype "passive"))
      (node (ref "R6") (pin "1") (pinfunction "1_1") (pintype "passive"))
    )
    (net (code "9") (name "Net-(4-PadOUT)") (class "Default")
      (node (ref "4") (pin "OUT") (pinfunction "OUT_OUT") (pintype "passive"))
      (node (ref "C12") (pin "2") (pinfunction "2_2") (pintype "passive"))
      (node (ref "JP3") (pin "7") (pinfunction "7_7") (pintype "passive"))
      (node (ref "JP3") (pin "8") (pinfunction "8_8") (pintype "passive"))
      (node (ref "R8") (pin "1") (pinfunction "1_1") (pintype "passive"))
    )
    (net (code "10") (name "Net-(5-PadOUT)") (class "Default")
      (node (ref "5") (pin "OUT") (pinfunction "OUT_OUT") (pintype "passive"))
      (node (ref "C14") (pin "1") (pinfunction "1_1") (pintype "passive"))
      (node (ref "JP3") (pin "5") (pinfunction "5_5") (pintype "passive"))
      (node (ref "JP3") (pin "6") (pinfunction "6_6") (pintype "passive"))
      (node (ref "R7") (pin "1") (pinfunction "1_1") (pintype "passive"))
    )
    (net (code "11") (name "Net-(6-PadOUT)") (class "Default")
      (node (ref "6") (pin "OUT") (pinfunction "OUT_OUT") (pintype "passive"))
      (node (ref "C13") (pin "2") (pinfunction "2_2") (pintype "passive"))
      (node (ref "JP3") (pin "15") (pinfunction "15_15") (pintype "passive"))
      (node (ref "JP3") (pin "16") (pinfunction "16_16") (pintype "passive"))
      (node (ref "R9") (pin "1") (pinfunction "1_1") (pintype "passive"))
    )
    (net (code "12") (name "Net-(7-PadOUT)") (class "Default")
      (node (ref "7") (pin "OUT") (pinfunction "OUT_OUT") (pintype "passive"))
      (node (ref "C19") (pin "2") (pinfunction "2_2") (pintype "passive"))
      (node (ref "JP4") (pin "7") (pinfunction "7_7") (pintype "passive"))
      (node (ref "JP4") (pin "8") (pinfunction "8_8") (pintype "passive"))
      (node (ref "R11") (pin "1") (pinfunction "1_1") (pintype "passive"))
    )
    (net (code "13") (name "Net-(8-PadOUT)") (class "Default")
      (node (ref "8") (pin "OUT") (pinfunction "OUT_OUT") (pintype "passive"))
      (node (ref "C21") (pin "1") (pinfunction "1_1") (pintype "passive"))
      (node (ref "JP4") (pin "5") (pinfunction "5_5") (pintype "passive"))
      (node (ref "JP4") (pin "6") (pinfunction "6_6") (pintype "passive"))
      (node (ref "R10") (pin "1") (pinfunction "1_1") (pintype "passive"))
    )
    (net (code "14") (name "Net-(9-PadOUT)") (class "Default")
      (node (ref "9") (pin "OUT") (pinfunction "OUT_OUT") (pintype "passive"))
      (node (ref "C20") (pin "2") (pinfunction "2_2") (pintype "passive"))
      (node (ref "JP4") (pin "15") (pinfunction "15_15") (pintype "passive"))
      (node (ref "JP4") (pin "16") (pinfunction "16_16") (pintype "passive"))
      (node (ref "R12") (pin "1") (pinfunction "1_1") (pintype "passive"))
    )
    (net (code "15") (name "Net-(10-PadOUT)") (class "Default")
      (node (ref "10") (pin "OUT") (pinfunction "OUT_OUT") (pintype "passive"))
      (node (ref "C24") (pin "2") (pinfunction "2_2") (pintype "passive"))
      (node (ref "JP5") (pin "7") (pinfunction "7_7") (pintype "passive"))
      (node (ref "JP5") (pin "8") (pinfunction "8_8") (pintype "passive"))
      (node (ref "R14") (pin "1") (pinfunction "1_1") (pintype "passive"))
    )
    (net (code "16") (name "Net-(11-PadOUT)") (class "Default")
      (node (ref "11") (pin "OUT") (pinfunction "OUT_OUT") (pintype "passive"))
      (node (ref "C26") (pin "1") (pinfunction "1_1") (pintype "passive"))
      (node (ref "JP5") (pin "5") (pinfunction "5_5") (pintype "passive"))
      (node (ref "JP5") (pin "6") (pinfunction "6_6") (pintype "passive"))
      (node (ref "R13") (pin "1") (pinfunction "1_1") (pintype "passive"))
    )
    (net (code "17") (name "Net-(12-PadOUT)") (class "Default")
      (node (ref "12") (pin "OUT") (pinfunction "OUT_OUT") (pintype "passive"))
      (node (ref "C25") (pin "2") (pinfunction "2_2") (pintype "passive"))
      (node (ref "JP5") (pin "15") (pinfunction "15_15") (pintype "passive"))
      (node (ref "JP5") (pin "16") (pinfunction "16_16") (pintype "passive"))
      (node (ref "R15") (pin "1") (pinfunction "1_1") (pintype "passive"))
    )
    (net (code "18") (name "Net-(13-PadOUT)") (class "Default")
      (node (ref "13") (pin "OUT") (pinfunction "OUT_OUT") (pintype "passive"))
      (node (ref "C29") (pin "2") (pinfunction "2_2") (pintype "passive"))
      (node (ref "JP6") (pin "7") (pinfunction "7_7") (pintype "passive"))
      (node (ref "JP6") (pin "8") (pinfunction "8_8") (pintype "passive"))
      (node (ref "R17") (pin "1") (pinfunction "1_1") (pintype "passive"))
    )
    (net (code "19") (name "Net-(14-PadOUT)") (class "Default")
      (node (ref "14") (pin "OUT") (pinfunction "OUT_OUT") (pintype "passive"))
      (node (ref "C31") (pin "1") (pinfunction "1_1") (pintype "passive"))
      (node (ref "JP6") (pin "5") (pinfunction "5_5") (pintype "passive"))
      (node (ref "JP6") (pin "6") (pinfunction "6_6") (pintype "passive"))
      (node (ref "R16") (pin "1") (pinfunction "1_1") (pintype "passive"))
    )
    (net (code "20") (name "Net-(15-PadOUT)") (class "Default")
      (node (ref "15") (pin "OUT") (pinfunction "OUT_OUT") (pintype "passive"))
      (node (ref "C30") (pin "2") (pinfunction "2_2") (pintype "passive"))
      (node (ref "JP6") (pin "15") (pinfunction "15_15") (pintype "passive"))
      (node (ref "JP6") (pin "16") (pinfunction "16_16") (pintype "passive"))
      (node (ref "R18") (pin "1") (pinfunction "1_1") (pintype "passive"))
    )
    (net (code "21") (name "Net-(7805-PadOUT)") (class "Default")
      (node (ref "7805") (pin "OUT") (pinfunction "OUT_OUT") (pintype "passive"))
      (node (ref "C15") (pin "1") (pinfunction "1_1") (pintype "passive"))
      (node (ref "JP1") (pin "5") (pinfunction "5_5") (pintype "passive"))
      (node (ref "JP1") (pin "6") (pinfunction "6_6") (pintype "passive"))
      (node (ref "R1") (pin "1") (pinfunction "1_1") (pintype "passive"))
    )
    (net (code "22") (name "Net-(7812-PadOUT)") (class "Default")
      (node (ref "7812") (pin "OUT") (pinfunction "OUT_OUT") (pintype "passive"))
      (node (ref "C1") (pin "2") (pinfunction "2_2") (pintype "passive"))
      (node (ref "JP1") (pin "7") (pinfunction "7_7") (pintype "passive"))
      (node (ref "JP1") (pin "8") (pinfunction "8_8") (pintype "passive"))
      (node (ref "R2") (pin "1") (pinfunction "1_1") (pintype "passive"))
    )
    (net (code "23") (name "Net-(7912-PadOUT)") (class "Default")
      (node (ref "7912") (pin "OUT") (pinfunction "OUT_OUT") (pintype "passive"))
      (node (ref "C2") (pin "2") (pinfunction "2_2") (pintype "passive"))
      (node (ref "JP1") (pin "15") (pinfunction "15_15") (pintype "passive"))
      (node (ref "JP1") (pin "16") (pinfunction "16_16") (pintype "passive"))
      (node (ref "R3") (pin "1") (pinfunction "1_1") (pintype "passive"))
    )
    (net (code "24") (name "Net-(C4-+)") (class "Default")
      (node (ref "7805") (pin "IN") (pinfunction "IN_IN") (pintype "input"))
      (node (ref "7812") (pin "IN") (pinfunction "IN_IN") (pintype "input"))
      (node (ref "C4") (pin "1") (pinfunction "+_1") (pintype "passive"))
      (node (ref "D1") (pin "C") (pinfunction "C_C") (pintype "passive"))
    )
    (net (code "25") (name "Net-(C5-+)") (class "Default")
      (node (ref "7912") (pin "IN") (pinfunction "IN_IN") (pintype "input"))
      (node (ref "C5") (pin "1") (pinfunction "+_1") (pintype "passive"))
      (node (ref "D2") (pin "A") (pinfunction "A_A") (pintype "passive"))
    )
    (net (code "26") (name "Net-(C8-+)") (class "Default")
      (node (ref "1") (pin "IN") (pinfunction "IN_IN") (pintype "input"))
      (node (ref "2") (pin "IN") (pinfunction "IN_IN") (pintype "input"))
      (node (ref "C8") (pin "1") (pinfunction "+_1") (pintype "passive"))
      (node (ref "D3") (pin "C") (pinfunction "C_C") (pintype "passive"))
    )
    (net (code "27") (name "Net-(C9-+)") (class "Default")
      (node (ref "3") (pin "IN") (pinfunction "IN_IN") (pintype "input"))
      (node (ref "C9") (pin "1") (pinfunction "+_1") (pintype "passive"))
      (node (ref "D4") (pin "A") (pinfunction "A_A") (pintype "passive"))
    )
    (net (code "28") (name "Net-(C16-+)") (class "Default")
      (node (ref "4") (pin "IN") (pinfunction "IN_IN") (pintype "input"))
      (node (ref "5") (pin "IN") (pinfunction "IN_IN") (pintype "input"))
      (node (ref "C16") (pin "1") (pinfunction "+_1") (pintype "passive"))
      (node (ref "D7") (pin "C") (pinfunction "C_C") (pintype "passive"))
    )
    (net (code "29") (name "Net-(C17-+)") (class "Default")
      (node (ref "6") (pin "IN") (pinfunction "IN_IN") (pintype "input"))
      (node (ref "C17") (pin "1") (pinfunction "+_1") (pintype "passive"))
      (node (ref "D8") (pin "A") (pinfunction "A_A") (pintype "passive"))
    )
    (net (code "30") (name "Net-(C18-+)") (class "Default")
      (node (ref "C18") (pin "1") (pinfunction "+_1") (pintype "passive"))
      (node (ref "LED1") (pin "K") (pinfunction "C_K") (pintype "passive"))
      (node (ref "LED10") (pin "K") (pinfunction "C_K") (pintype "passive"))
      (node (ref "LED11") (pin "K") (pinfunction "C_K") (pintype "passive"))
      (node (ref "LED12") (pin "A") (pinfunction "A_A") (pintype "passive"))
      (node (ref "LED13") (pin "K") (pinfunction "C_K") (pintype "passive"))
      (node (ref "LED14") (pin "K") (pinfunction "C_K") (pintype "passive"))
      (node (ref "LED15") (pin "A") (pinfunction "A_A") (pintype "passive"))
      (node (ref "LED16") (pin "K") (pinfunction "C_K") (pintype "passive"))
      (node (ref "LED17") (pin "K") (pinfunction "C_K") (pintype "passive"))
      (node (ref "LED18") (pin "A") (pinfunction "A_A") (pintype "passive"))
      (node (ref "LED2") (pin "K") (pinfunction "C_K") (pintype "passive"))
      (node (ref "LED3") (pin "A") (pinfunction "A_A") (pintype "passive"))
      (node (ref "LED4") (pin "K") (pinfunction "C_K") (pintype "passive"))
      (node (ref "LED5") (pin "K") (pinfunction "C_K") (pintype "passive"))
      (node (ref "LED6") (pin "A") (pinfunction "A_A") (pintype "passive"))
      (node (ref "LED7") (pin "K") (pinfunction "C_K") (pintype "passive"))
      (node (ref "LED8") (pin "K") (pinfunction "C_K") (pintype "passive"))
      (node (ref "LED9") (pin "A") (pinfunction "A_A") (pintype "passive"))
      (node (ref "S1") (pin "P") (pinfunction "P_P") (pintype "passive"))
    )
    (net (code "31") (name "Net-(C22-+)") (class "Default")
      (node (ref "7") (pin "IN") (pinfunction "IN_IN") (pintype "input"))
      (node (ref "8") (pin "IN") (pinfunction "IN_IN") (pintype "input"))
      (node (ref "C22") (pin "1") (pinfunction "+_1") (pintype "passive"))
      (node (ref "D9") (pin "C") (pinfunction "C_C") (pintype "passive"))
    )
    (net (code "32") (name "Net-(C23-+)") (class "Default")
      (node (ref "9") (pin "IN") (pinfunction "IN_IN") (pintype "input"))
      (node (ref "C23") (pin "1") (pinfunction "+_1") (pintype "passive"))
      (node (ref "D10") (pin "A") (pinfunction "A_A") (pintype "passive"))
    )
    (net (code "33") (name "Net-(C27-+)") (class "Default")
      (node (ref "10") (pin "IN") (pinfunction "IN_IN") (pintype "input"))
      (node (ref "11") (pin "IN") (pinfunction "IN_IN") (pintype "input"))
      (node (ref "C27") (pin "1") (pinfunction "+_1") (pintype "passive"))
      (node (ref "D11") (pin "C") (pinfunction "C_C") (pintype "passive"))
    )
    (net (code "34") (name "Net-(C28-+)") (class "Default")
      (node (ref "12") (pin "IN") (pinfunction "IN_IN") (pintype "input"))
      (node (ref "C28") (pin "1") (pinfunction "+_1") (pintype "passive"))
      (node (ref "D12") (pin "A") (pinfunction "A_A") (pintype "passive"))
    )
    (net (code "35") (name "Net-(C32-+)") (class "Default")
      (node (ref "13") (pin "IN") (pinfunction "IN_IN") (pintype "input"))
      (node (ref "14") (pin "IN") (pinfunction "IN_IN") (pintype "input"))
      (node (ref "C32") (pin "1") (pinfunction "+_1") (pintype "passive"))
      (node (ref "D13") (pin "C") (pinfunction "C_C") (pintype "passive"))
    )
    (net (code "36") (name "Net-(C33-+)") (class "Default")
      (node (ref "15") (pin "IN") (pinfunction "IN_IN") (pintype "input"))
      (node (ref "C33") (pin "1") (pinfunction "+_1") (pintype "passive"))
      (node (ref "D14") (pin "A") (pinfunction "A_A") (pintype "passive"))
    )
    (net (code "37") (name "Net-(F1-2)") (class "Default")
      (node (ref "F1") (pin "P$2") (pinfunction "2_P$2") (pintype "bidirectional"))
      (node (ref "U$1") (pin "1") (pinfunction "1_1") (pintype "passive"))
    )
    (net (code "38") (name "Net-(F2-2)") (class "Default")
      (node (ref "F2") (pin "P$2") (pinfunction "2_P$2") (pintype "bidirectional"))
      (node (ref "U$2") (pin "1") (pinfunction "1_1") (pintype "passive"))
    )
    (net (code "39") (name "Net-(LED1-PadA)") (class "Default")
      (node (ref "LED1") (pin "A") (pinfunction "A_A") (pintype "passive"))
      (node (ref "R1") (pin "2") (pinfunction "2_2") (pintype "passive"))
    )
    (net (code "40") (name "Net-(LED2-PadA)") (class "Default")
      (node (ref "LED2") (pin "A") (pinfunction "A_A") (pintype "passive"))
      (node (ref "R2") (pin "2") (pinfunction "2_2") (pintype "passive"))
    )
    (net (code "41") (name "Net-(LED3-C)") (class "Default")
      (node (ref "LED3") (pin "K") (pinfunction "C_K") (pintype "passive"))
      (node (ref "R3") (pin "2") (pinfunction "2_2") (pintype "passive"))
    )
    (net (code "42") (name "Net-(LED4-PadA)") (class "Default")
      (node (ref "LED4") (pin "A") (pinfunction "A_A") (pintype "passive"))
      (node (ref "R4") (pin "2") (pinfunction "2_2") (pintype "passive"))
    )
    (net (code "43") (name "Net-(LED5-PadA)") (class "Default")
      (node (ref "LED5") (pin "A") (pinfunction "A_A") (pintype "passive"))
      (node (ref "R5") (pin "2") (pinfunction "2_2") (pintype "passive"))
    )
    (net (code "44") (name "Net-(LED6-C)") (class "Default")
      (node (ref "LED6") (pin "K") (pinfunction "C_K") (pintype "passive"))
      (node (ref "R6") (pin "2") (pinfunction "2_2") (pintype "passive"))
    )
    (net (code "45") (name "Net-(LED7-PadA)") (class "Default")
      (node (ref "LED7") (pin "A") (pinfunction "A_A") (pintype "passive"))
      (node (ref "R7") (pin "2") (pinfunction "2_2") (pintype "passive"))
    )
    (net (code "46") (name "Net-(LED8-PadA)") (class "Default")
      (node (ref "LED8") (pin "A") (pinfunction "A_A") (pintype "passive"))
      (node (ref "R8") (pin "2") (pinfunction "2_2") (pintype "passive"))
    )
    (net (code "47") (name "Net-(LED9-C)") (class "Default")
      (node (ref "LED9") (pin "K") (pinfunction "C_K") (pintype "passive"))
      (node (ref "R9") (pin "2") (pinfunction "2_2") (pintype "passive"))
    )
    (net (code "48") (name "Net-(LED10-PadA)") (class "Default")
      (node (ref "LED10") (pin "A") (pinfunction "A_A") (pintype "passive"))
      (node (ref "R10") (pin "2") (pinfunction "2_2") (pintype "passive"))
    )
    (net (code "49") (name "Net-(LED11-PadA)") (class "Default")
      (node (ref "LED11") (pin "A") (pinfunction "A_A") (pintype "passive"))
      (node (ref "R11") (pin "2") (pinfunction "2_2") (pintype "passive"))
    )
    (net (code "50") (name "Net-(LED12-C)") (class "Default")
      (node (ref "LED12") (pin "K") (pinfunction "C_K") (pintype "passive"))
      (node (ref "R12") (pin "2") (pinfunction "2_2") (pintype "passive"))
    )
    (net (code "51") (name "Net-(LED13-PadA)") (class "Default")
      (node (ref "LED13") (pin "A") (pinfunction "A_A") (pintype "passive"))
      (node (ref "R13") (pin "2") (pinfunction "2_2") (pintype "passive"))
    )
    (net (code "52") (name "Net-(LED14-PadA)") (class "Default")
      (node (ref "LED14") (pin "A") (pinfunction "A_A") (pintype "passive"))
      (node (ref "R14") (pin "2") (pinfunction "2_2") (pintype "passive"))
    )
    (net (code "53") (name "Net-(LED15-C)") (class "Default")
      (node (ref "LED15") (pin "K") (pinfunction "C_K") (pintype "passive"))
      (node (ref "R15") (pin "2") (pinfunction "2_2") (pintype "passive"))
    )
    (net (code "54") (name "Net-(LED16-PadA)") (class "Default")
      (node (ref "LED16") (pin "A") (pinfunction "A_A") (pintype "passive"))
      (node (ref "R16") (pin "2") (pinfunction "2_2") (pintype "passive"))
    )
    (net (code "55") (name "Net-(LED17-PadA)") (class "Default")
      (node (ref "LED17") (pin "A") (pinfunction "A_A") (pintype "passive"))
      (node (ref "R17") (pin "2") (pinfunction "2_2") (pintype "passive"))
    )
    (net (code "56") (name "Net-(LED18-C)") (class "Default")
      (node (ref "LED18") (pin "K") (pinfunction "C_K") (pintype "passive"))
      (node (ref "R18") (pin "2") (pinfunction "2_2") (pintype "passive"))
    )
    (net (code "57") (name "unconnected-(JP1-Pad1)") (class "Default")
      (node (ref "JP1") (pin "1") (pinfunction "1_1") (pintype "passive"))
    )
    (net (code "58") (name "unconnected-(JP1-Pad2)") (class "Default")
      (node (ref "JP1") (pin "2") (pinfunction "2_2") (pintype "passive"))
    )
    (net (code "59") (name "unconnected-(JP1-Pad3)") (class "Default")
      (node (ref "JP1") (pin "3") (pinfunction "3_3") (pintype "passive"))
    )
    (net (code "60") (name "unconnected-(JP1-Pad4)") (class "Default")
      (node (ref "JP1") (pin "4") (pinfunction "4_4") (pintype "passive"))
    )
    (net (code "61") (name "unconnected-(JP2-Pad1)") (class "Default")
      (node (ref "JP2") (pin "1") (pinfunction "1_1") (pintype "passive"))
    )
    (net (code "62") (name "unconnected-(JP2-Pad2)") (class "Default")
      (node (ref "JP2") (pin "2") (pinfunction "2_2") (pintype "passive"))
    )
    (net (code "63") (name "unconnected-(JP2-Pad3)") (class "Default")
      (node (ref "JP2") (pin "3") (pinfunction "3_3") (pintype "passive"))
    )
    (net (code "64") (name "unconnected-(JP2-Pad4)") (class "Default")
      (node (ref "JP2") (pin "4") (pinfunction "4_4") (pintype "passive"))
    )
    (net (code "65") (name "unconnected-(JP3-Pad1)") (class "Default")
      (node (ref "JP3") (pin "1") (pinfunction "1_1") (pintype "passive"))
    )
    (net (code "66") (name "unconnected-(JP3-Pad2)") (class "Default")
      (node (ref "JP3") (pin "2") (pinfunction "2_2") (pintype "passive"))
    )
    (net (code "67") (name "unconnected-(JP3-Pad3)") (class "Default")
      (node (ref "JP3") (pin "3") (pinfunction "3_3") (pintype "passive"))
    )
    (net (code "68") (name "unconnected-(JP3-Pad4)") (class "Default")
      (node (ref "JP3") (pin "4") (pinfunction "4_4") (pintype "passive"))
    )
    (net (code "69") (name "unconnected-(JP4-Pad1)") (class "Default")
      (node (ref "JP4") (pin "1") (pinfunction "1_1") (pintype "passive"))
    )
    (net (code "70") (name "unconnected-(JP4-Pad2)") (class "Default")
      (node (ref "JP4") (pin "2") (pinfunction "2_2") (pintype "passive"))
    )
    (net (code "71") (name "unconnected-(JP4-Pad3)") (class "Default")
      (node (ref "JP4") (pin "3") (pinfunction "3_3") (pintype "passive"))
    )
    (net (code "72") (name "unconnected-(JP4-Pad4)") (class "Default")
      (node (ref "JP4") (pin "4") (pinfunction "4_4") (pintype "passive"))
    )
    (net (code "73") (name "unconnected-(JP5-Pad1)") (class "Default")
      (node (ref "JP5") (pin "1") (pinfunction "1_1") (pintype "passive"))
    )
    (net (code "74") (name "unconnected-(JP5-Pad2)") (class "Default")
      (node (ref "JP5") (pin "2") (pinfunction "2_2") (pintype "passive"))
    )
    (net (code "75") (name "unconnected-(JP5-Pad3)") (class "Default")
      (node (ref "JP5") (pin "3") (pinfunction "3_3") (pintype "passive"))
    )
    (net (code "76") (name "unconnected-(JP5-Pad4)") (class "Default")
      (node (ref "JP5") (pin "4") (pinfunction "4_4") (pintype "passive"))
    )
    (net (code "77") (name "unconnected-(JP6-Pad1)") (class "Default")
      (node (ref "JP6") (pin "1") (pinfunction "1_1") (pintype "passive"))
    )
    (net (code "78") (name "unconnected-(JP6-Pad2)") (class "Default")
      (node (ref "JP6") (pin "2") (pinfunction "2_2") (pintype "passive"))
    )
    (net (code "79") (name "unconnected-(JP6-Pad3)") (class "Default")
      (node (ref "JP6") (pin "3") (pinfunction "3_3") (pintype "passive"))
    )
    (net (code "80") (name "unconnected-(JP6-Pad4)") (class "Default")
      (node (ref "JP6") (pin "4") (pinfunction "4_4") (pintype "passive"))
    )
    (net (code "81") (name "unconnected-(S1-PadS)") (class "Default")
      (node (ref "S1") (pin "S") (pinfunction "S_S") (pintype "passive"))
    )
  )
)
